# top.net
KiCad netlist of a schematic drawn in Altium Designer
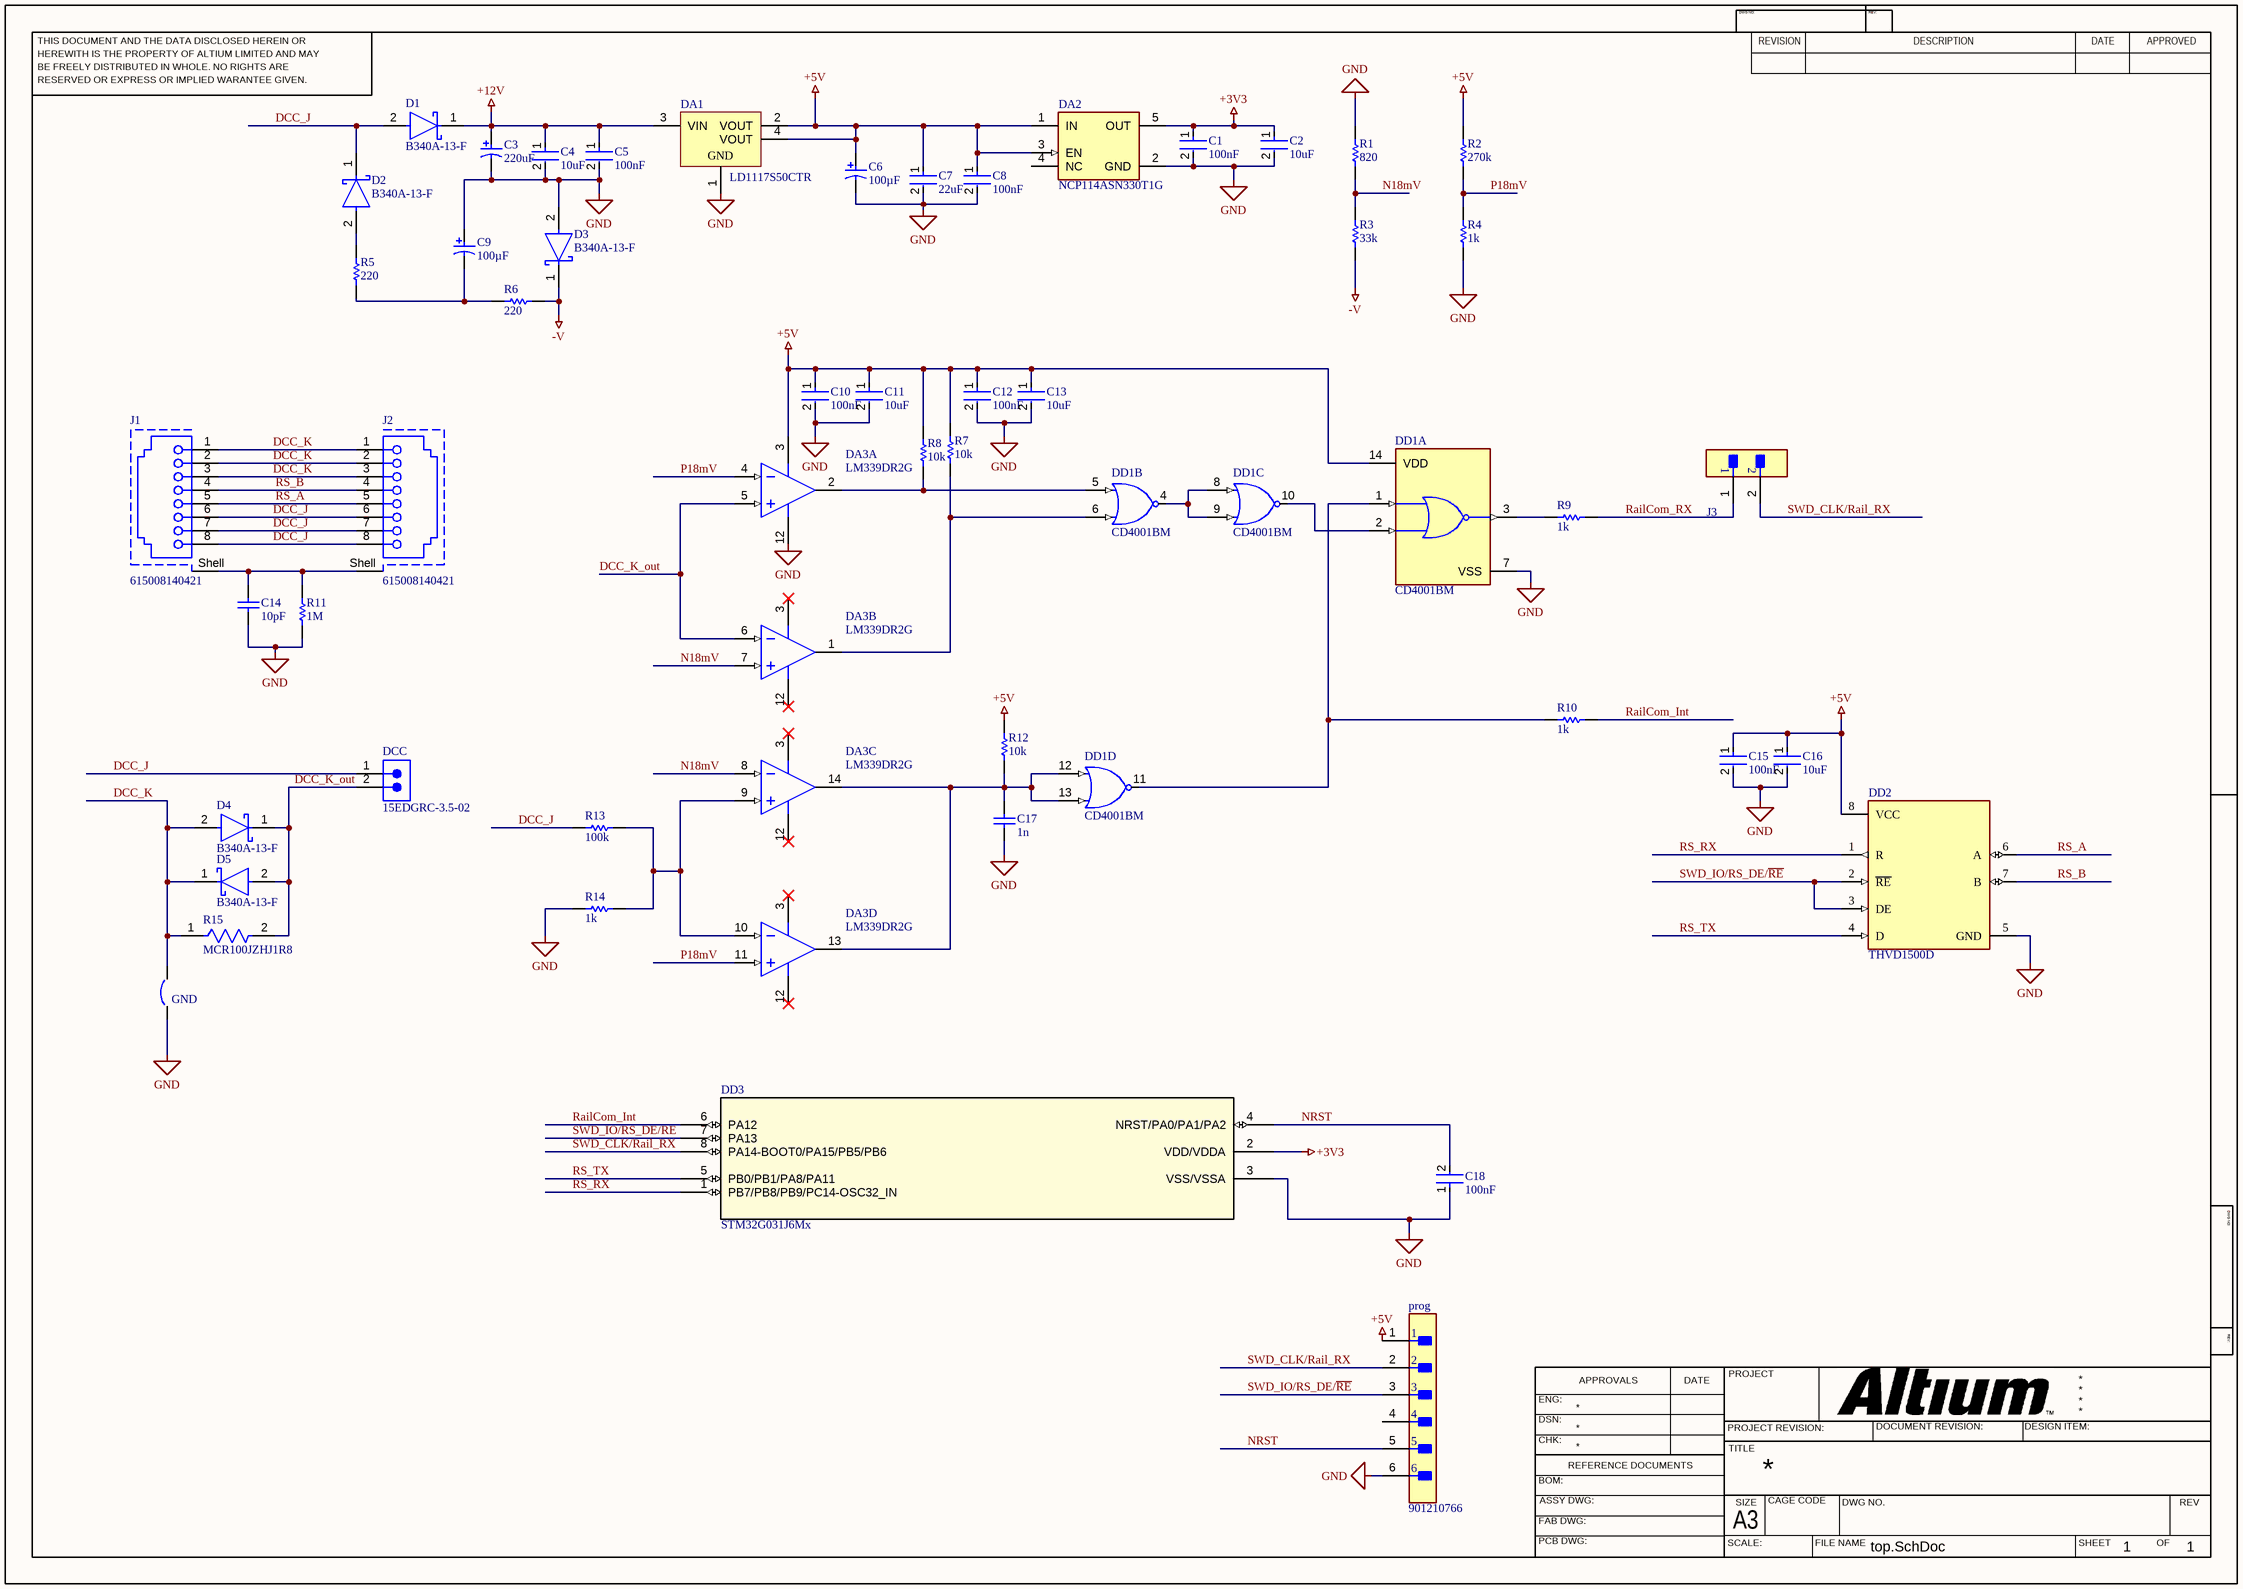
[diagram p0: top.SchDoc]

(export (version "E")
  (design (tool "Eeschema 10.0.6"))
  (components
    (comp (ref "C1")
      (value "CGA3E2X7R1H104K080AA")
      (footprint "FP-CGA3E-0_3-0_1-IPC_C")
      (description "Cap Ceramic 100nF 50V X7R 10% Pad SMD 0603 +125°C Automotive T/R")
      (fields
        (field (name "TOLERANCE") "10%")
        (field (name "CAPACITANCE") "100nF")
        (field (name "VOLTAGE") "50V")
      )
      (libsource (lib "Altium Content Vault") (part "b4654b650e69147ec39a6b967a45e02"))
    )
    (comp (ref "C2")
      (value "GRM188R60J106ME47D")
      (footprint "FP-GRM188-0_1-e0_2_0_55-IPC_C")
      (description "Chip Multilayer Ceramic Capacitors for General Purpose, 0603, 10uF, X5R, 15%, 20%, 6.3V")
      (fields
        (field (name "CAPACITANCE") "10uF")
        (field (name "VOLTAGE") "6.3V")
        (field (name "TOLERANCE") "20%")
      )
      (libsource (lib "Altium Content Vault") (part "02cd4be3c70576c341d710602a673aa"))
    )
    (comp (ref "C3")
      (value "220uF")
      (footprint "PNSC-EEE-FK1E221P_N")
      (fields (field (name "MANUFACTURER") "Panasonic") (field (name "Comment") "EEE-FK1E221P"))
      (libsource (lib "Altium Content Vault") (part "CAP-P-2"))
    )
    (comp (ref "C4")
      (value "GRM188R60J106ME47D")
      (footprint "FP-GRM188-0_1-e0_2_0_55-IPC_C")
      (description "Chip Multilayer Ceramic Capacitors for General Purpose, 0603, 10uF, X5R, 15%, 20%, 6.3V")
      (fields
        (field (name "CAPACITANCE") "10uF")
        (field (name "VOLTAGE") "6.3V")
        (field (name "TOLERANCE") "20%")
      )
      (libsource (lib "Altium Content Vault") (part "02cd4be3c70576c341d710602a673aa"))
    )
    (comp (ref "C5")
      (value "CGA3E2X7R1H104K080AA")
      (footprint "FP-CGA3E-0_3-0_1-IPC_C")
      (description "Cap Ceramic 100nF 50V X7R 10% Pad SMD 0603 +125°C Automotive T/R")
      (fields
        (field (name "TOLERANCE") "10%")
        (field (name "CAPACITANCE") "100nF")
        (field (name "VOLTAGE") "50V")
      )
      (libsource (lib "Altium Content Vault") (part "b4654b650e69147ec39a6b967a45e02"))
    )
    (comp (ref "C6")
      (value "EEEFK1E101XP")
      (footprint "PNSC-FK-V-D8_V")
      (fields (field (name "CAPACITANCE") "100µF") (field (name "MANUFACTURER") "Panasonic"))
      (libsource (lib "Altium Content Vault") (part "CAP-P-2"))
    )
    (comp (ref "C7")
      (value "GRM188R61A226ME15D")
      (footprint "FP-GRM188-0_2-IPC_C")
      (description "Chip Multilayer Ceramic Capacitors for General Purpose, 0603, 22uF, X5R, 15%, 20%, 10V")
      (fields (field (name "TOLERANCE") "20%") (field (name "CAPACITANCE") "22uF"))
      (libsource (lib "Altium Content Vault") (part "11868f565c42a9108669ba33697ecf6"))
    )
    (comp (ref "C8")
      (value "CGA3E2X7R1H104K080AA")
      (footprint "FP-CGA3E-0_3-0_1-IPC_C")
      (description "Cap Ceramic 100nF 50V X7R 10% Pad SMD 0603 +125°C Automotive T/R")
      (fields
        (field (name "TOLERANCE") "10%")
        (field (name "CAPACITANCE") "100nF")
        (field (name "VOLTAGE") "50V")
      )
      (libsource (lib "Altium Content Vault") (part "b4654b650e69147ec39a6b967a45e02"))
    )
    (comp (ref "C9")
      (value "EEEFK1E101XP")
      (footprint "PNSC-FK-V-D8_V")
      (fields (field (name "CAPACITANCE") "100µF") (field (name "MANUFACTURER") "Panasonic"))
      (libsource (lib "Altium Content Vault") (part "CAP-P-2"))
    )
    (comp (ref "C10")
      (value "CGA3E2X7R1H104K080AA")
      (footprint "FP-CGA3E-0_3-0_1-IPC_C")
      (description "Cap Ceramic 100nF 50V X7R 10% Pad SMD 0603 +125°C Automotive T/R")
      (fields
        (field (name "TOLERANCE") "10%")
        (field (name "CAPACITANCE") "100nF")
        (field (name "VOLTAGE") "50V")
      )
      (libsource (lib "Altium Content Vault") (part "b4654b650e69147ec39a6b967a45e02"))
    )
    (comp (ref "C11")
      (value "GRM188R60J106ME47D")
      (footprint "FP-GRM188-0_1-e0_2_0_55-IPC_C")
      (description "Chip Multilayer Ceramic Capacitors for General Purpose, 0603, 10uF, X5R, 15%, 20%, 6.3V")
      (fields
        (field (name "CAPACITANCE") "10uF")
        (field (name "VOLTAGE") "6.3V")
        (field (name "TOLERANCE") "20%")
      )
      (libsource (lib "Altium Content Vault") (part "02cd4be3c70576c341d710602a673aa"))
    )
    (comp (ref "C12")
      (value "CGA3E2X7R1H104K080AA")
      (footprint "FP-CGA3E-0_3-0_1-IPC_C")
      (description "Cap Ceramic 100nF 50V X7R 10% Pad SMD 0603 +125°C Automotive T/R")
      (fields
        (field (name "TOLERANCE") "10%")
        (field (name "CAPACITANCE") "100nF")
        (field (name "VOLTAGE") "50V")
      )
      (libsource (lib "Altium Content Vault") (part "b4654b650e69147ec39a6b967a45e02"))
    )
    (comp (ref "C13")
      (value "GRM188R60J106ME47D")
      (footprint "FP-GRM188-0_1-e0_2_0_55-IPC_C")
      (description "Chip Multilayer Ceramic Capacitors for General Purpose, 0603, 10uF, X5R, 15%, 20%, 6.3V")
      (fields
        (field (name "CAPACITANCE") "10uF")
        (field (name "VOLTAGE") "6.3V")
        (field (name "TOLERANCE") "20%")
      )
      (libsource (lib "Altium Content Vault") (part "02cd4be3c70576c341d710602a673aa"))
    )
    (comp (ref "C14")
      (value "10pF")
      (footprint "CAPC0603(1608)100_N")
      (description "CAP 10pF 25V ±1% 0603 (1608 Metric) Thickness 1mm SMD")
      (fields (field (name "TOLERANCE") "Â±1%") (field (name "Comment") "CAP 10pF 25V 0603(1608)"))
      (libsource (lib "Altium Content Vault") (part "CAP"))
    )
    (comp (ref "C15")
      (value "CGA3E2X7R1H104K080AA")
      (footprint "FP-CGA3E-0_3-0_1-IPC_C")
      (description "Cap Ceramic 100nF 50V X7R 10% Pad SMD 0603 +125°C Automotive T/R")
      (fields
        (field (name "TOLERANCE") "10%")
        (field (name "CAPACITANCE") "100nF")
        (field (name "VOLTAGE") "50V")
      )
      (libsource (lib "Altium Content Vault") (part "b4654b650e69147ec39a6b967a45e02"))
    )
    (comp (ref "C16")
      (value "GRM188R60J106ME47D")
      (footprint "FP-GRM188-0_1-e0_2_0_55-IPC_C")
      (description "Chip Multilayer Ceramic Capacitors for General Purpose, 0603, 10uF, X5R, 15%, 20%, 6.3V")
      (fields
        (field (name "CAPACITANCE") "10uF")
        (field (name "VOLTAGE") "6.3V")
        (field (name "TOLERANCE") "20%")
      )
      (libsource (lib "Altium Content Vault") (part "02cd4be3c70576c341d710602a673aa"))
    )
    (comp (ref "C17")
      (value "1n")
      (footprint "CAPC1608X90X35NL10T15")
      (fields (field (name "PART NUMBER") "GRM188R71H102KA01D") (field (name "MANUFACTURER") "Murata"))
      (libsource (lib "Altium Content Vault") (part "CAP"))
    )
    (comp (ref "C18")
      (value "CGA3E2X7R1H104K080AA")
      (footprint "FP-CGA3E-0_3-0_1-MFG")
      (description "Cap Ceramic 100nF 50V X7R 10% Pad SMD 0603 +125°C Automotive T/R")
      (fields
        (field (name "TOLERANCE") "10%")
        (field (name "CAPACITANCE") "100nF")
        (field (name "VOLTAGE") "50V")
      )
      (libsource (lib "Altium Content Vault") (part "b4654b650e69147ec39a6b967a45e02"))
    )
    (comp (ref "D1")
      (value "B340A-13-F")
      (footprint "FP-SMA-MFG")
      (description "DIODE SCHOTTKY 40V 3A SMA")
      (fields (field (name "VOLTAGE") "40V"))
      (libsource (lib "Altium Content Vault") (part "1d6ec82d83fb6aee721767c19dac4b9"))
    )
    (comp (ref "D2")
      (value "B340A-13-F")
      (footprint "FP-SMA-MFG")
      (description "DIODE SCHOTTKY 40V 3A SMA")
      (fields (field (name "VOLTAGE") "40V"))
      (libsource (lib "Altium Content Vault") (part "1d6ec82d83fb6aee721767c19dac4b9"))
    )
    (comp (ref "D3")
      (value "B340A-13-F")
      (footprint "FP-SMA-MFG")
      (description "DIODE SCHOTTKY 40V 3A SMA")
      (fields (field (name "VOLTAGE") "40V"))
      (libsource (lib "Altium Content Vault") (part "1d6ec82d83fb6aee721767c19dac4b9"))
    )
    (comp (ref "D4")
      (value "B340A-13-F")
      (footprint "FP-SMA-MFG")
      (description "DIODE SCHOTTKY 40V 3A SMA")
      (fields (field (name "VOLTAGE") "40V"))
      (libsource (lib "Altium Content Vault") (part "1d6ec82d83fb6aee721767c19dac4b9"))
    )
    (comp (ref "D5")
      (value "B340A-13-F")
      (footprint "FP-SMA-MFG")
      (description "DIODE SCHOTTKY 40V 3A SMA")
      (fields (field (name "VOLTAGE") "40V"))
      (libsource (lib "Altium Content Vault") (part "1d6ec82d83fb6aee721767c19dac4b9"))
    )
    (comp (ref "DA1")
      (value "LD1117S50CTR")
      (footprint "SOT-223_N")
      (description "Fixed Low Drop Positive Voltage Regulator, 5V, 4-Pin SOT-223, Tape and Reel")
      (libsource (lib "Altium Content Vault") (part "PM-REG-LD1117-SOT4"))
    )
    (comp (ref "DA2")
      (value "NCP114ASN330T1G")
      (footprint "FP-483-MFG")
      (description "IC REG LINEAR 3.3V 300MA 5TSOP")
      (fields
        (field (name "MANUFACTURER") "ON Semiconductor")
        (field (name "OCTOPART") "https://octopart.com/ncp114asn330t1g-on+semiconductor-74628742")
      )
      (libsource (lib "Altium Content Vault") (part "57814aa37072aacea77ef0fe9350350"))
    )
    (comp (ref "DA3")
      (value "LM339DR2G")
      (footprint "ONSC-SOIC-14-751A-03_V")
      (description "Single Supply Quad Comparators, 0 to 70 degC, 14-Pin SOIC, Pb-Free, Tape and Reel")
      (fields (field (name "MANUFACTURER") "On Semiconductor"))
      (libsource (lib "Altium Content Vault") (part "ONSC-LM239_LM339_LM2901_NCV2901_MC3302_LMV339-14"))
    )
    (comp (ref "DCC")
      (value "15EDGRC-3.5-02")
      (footprint "691305140002")
      (libsource (lib "Altium Content Vault") (part "TBL - 1R - 02P - Male"))
    )
    (comp (ref "DD1")
      (value "CD4001BM")
      (footprint "FP-D0014A-MFG")
      (description "IC GATE NOR 4CH 2-INP 14SOIC")
      (libsource (lib "Altium Content Vault") (part "2cf6dc1d20626fb6062ed3edb113d6e"))
    )
    (comp (ref "DD2")
      (value "THVD1500D")
      (footprint "FP-D0008B-IPC_A")
      (description "IC TRANSCEIVER HALF 1/1 8SOIC")
      (libsource (lib "Altium Content Vault") (part "2959008ed950a7d942df01a48597072"))
    )
    (comp (ref "DD3")
      (value "STM32G031J6Mx")
      (footprint "SO-8")
      (fields
        (field (name "MANUFACTURER_PART_NUMBER") "stm32g0_so8_t1")
        (field (name "COPYRIGHT") "Copyright (C) 2018 Accelerated Designs. All rights reserved")
      )
      (libsource (lib "ST Microelectronics STM32 G0") (part "STM32G031J6Mx"))
    )
    (comp (ref "GND")
      (value "~")
      (footprint "JP_SMD")
      (description "Circuit Breaker")
      (fields (field (name "PUBLISHER") "Altium Limited"))
      (libsource (lib "test_adc") (part "Circuit Breaker"))
    )
    (comp (ref "J1")
      (value "615008140421")
      (footprint "615008140421")
      (libsource (lib "Altium Content Vault") (part "8P8C - 1 Port - Shielded"))
    )
    (comp (ref "J2")
      (value "615008140421")
      (footprint "615008140421")
      (libsource (lib "Altium Content Vault") (part "8P8C - 1 Port - Shielded"))
    )
    (comp (ref "J3")
      (value "M20-9990245")
      (footprint "FP-M20-9990245-MFG")
      (description "CONN HEADER VERT 2POS 2.54MM")
      (fields (field (name "VOLTAGE") "50V"))
      (libsource (lib "Altium Content Vault") (part "3bc925449376181038e59eaffc5286c"))
    )
    (comp (ref "prog")
      (value "901210766")
      (footprint "FP-901210766-MFG")
      (description "CONN HEADER R/A 6POS 2.54MM")
      (fields
        (field (name "MANUFACTURER") "Molex")
        (field (name "OCTOPART") "https://octopart.com/90121-0766-molex-655456")
      )
      (libsource (lib "Altium Content Vault") (part "f2cb566baf1c37ab5a3b8e90bbeafd6"))
    )
    (comp (ref "R1")
      (value "820")
      (footprint "RESC1608X55X30NL15T15")
      (fields (field (name "MANUFACTURER") "Panasonic") (field (name "PART NUMBER") "ERJ3EKF8203V"))
      (libsource (lib "Altium Content Vault") (part "RES"))
    )
    (comp (ref "R2")
      (value "270k")
      (footprint "RESC1608X55X30NL20T10")
      (fields (field (name "PART NUMBER") "RK73H1JTTD2703F") (field (name "MANUFACTURER") "KOA Speer"))
      (libsource (lib "Altium Content Vault") (part "RES"))
    )
    (comp (ref "R3")
      (value "33k")
      (footprint "RESC1608X55X30NL20T20")
      (fields (field (name "PART NUMBER") "ERA3AEB333V") (field (name "MANUFACTURER") "Panasonic"))
      (libsource (lib "Altium Content Vault") (part "RES"))
    )
    (comp (ref "R4")
      (value "1k")
      (footprint "RESC1608X55X30NL15T15")
      (fields (field (name "PART NUMBER") "ERJ-3EKF1001V") (field (name "MANUFACTURER") "Panasonic"))
      (libsource (lib "Altium Content Vault") (part "RES"))
    )
    (comp (ref "R5")
      (value "220")
      (footprint "RESC1608X55X30NL15T15")
      (description "Chip Resistor, 220 Ohm, +/- 1%, 0.1 W, -55 to 155 degC, 0603 (1608 Metric), RoHS, Tape and Reel")
      (fields (field (name "TOLERANCE") "1%") (field (name "Comment") "ERJ-3EKF2200V"))
      (libsource (lib "Altium Content Vault") (part "RES-2"))
    )
    (comp (ref "R6")
      (value "220")
      (footprint "RESC1608X55X30NL15T15")
      (description "Chip Resistor, 220 Ohm, +/- 1%, 0.1 W, -55 to 155 degC, 0603 (1608 Metric), RoHS, Tape and Reel")
      (fields (field (name "TOLERANCE") "1%") (field (name "Comment") "ERJ-3EKF2200V"))
      (libsource (lib "Altium Content Vault") (part "RES-2"))
    )
    (comp (ref "R7")
      (value "10k")
      (footprint "RESC1609X55X30NL15T15")
      (description "Chip Resistor, 10 KOhm, +/- 1%, 0.1 W, -55 to 155 degC, 0603 (1608 Metric), RoHS, Tape and Reel")
      (fields (field (name "TOLERANCE") "1%") (field (name "MANUFACTURER") "Panasonic"))
      (libsource (lib "Altium Content Vault") (part "RES-2"))
    )
    (comp (ref "R8")
      (value "10k")
      (footprint "RESC1609X55X30NL15T15")
      (description "Chip Resistor, 10 KOhm, +/- 1%, 0.1 W, -55 to 155 degC, 0603 (1608 Metric), RoHS, Tape and Reel")
      (fields (field (name "TOLERANCE") "1%") (field (name "MANUFACTURER") "Panasonic"))
      (libsource (lib "Altium Content Vault") (part "RES-2"))
    )
    (comp (ref "R9")
      (value "1k")
      (footprint "RESC1608X55X30NL15T15")
      (fields (field (name "PART NUMBER") "ERJ-3EKF1001V") (field (name "MANUFACTURER") "Panasonic"))
      (libsource (lib "Altium Content Vault") (part "RES"))
    )
    (comp (ref "R10")
      (value "1k")
      (footprint "RESC1608X55X30NL15T15")
      (fields (field (name "PART NUMBER") "ERJ-3EKF1001V") (field (name "MANUFACTURER") "Panasonic"))
      (libsource (lib "Altium Content Vault") (part "RES"))
    )
    (comp (ref "R11")
      (value "1M")
      (footprint "RESC1608X55X25NL10T15")
      (description "Chip Resistor, 1 MOhm, +/- 1%, 100 mW, -55 to 155 degC, 0603 (1608 Metric), RoHS, Tape and Reel")
      (fields (field (name "TOLERANCE") "20%") (field (name "Comment") "RC0603FR-071ML"))
      (libsource (lib "Altium Content Vault") (part "RES-2"))
    )
    (comp (ref "R12")
      (value "10k")
      (footprint "RESC1609X55X30NL15T15")
      (description "Chip Resistor, 10 KOhm, +/- 1%, 0.1 W, -55 to 155 degC, 0603 (1608 Metric), RoHS, Tape and Reel")
      (fields (field (name "TOLERANCE") "1%") (field (name "MANUFACTURER") "Panasonic"))
      (libsource (lib "Altium Content Vault") (part "RES-2"))
    )
    (comp (ref "R13")
      (value "100k")
      (footprint "RESC1608X55X30NL15T15")
      (fields (field (name "PART NUMBER") "ERJ-3EKF1003V") (field (name "MANUFACTURER") "Panasonic"))
      (libsource (lib "Altium Content Vault") (part "RES"))
    )
    (comp (ref "R14")
      (value "1k")
      (footprint "RESC1608X55X30NL15T15")
      (fields (field (name "PART NUMBER") "ERJ-3EKF1001V") (field (name "MANUFACTURER") "Panasonic"))
      (libsource (lib "Altium Content Vault") (part "RES"))
    )
    (comp (ref "R15")
      (value "MCR100JZHJ1R8")
      (footprint "FP-MCR100-IPC_C")
      (description "Thick Film Chip Resistor, 2512, 1.8Ω, 5%, +850/+150ppm/°C, 1W, 200V")
      (fields (field (name "TOLERANCE") "5%"))
      (libsource (lib "Altium Content Vault") (part "1029c3af85768c4190bb7ad29bc67b5"))
    )
  )
  (nets
    (net (code "1") (name "+3V3") (class "Default")
      (node (ref "C1") (pin "1") (pinfunction "1_1") (pintype "passive"))
      (node (ref "C2") (pin "1") (pinfunction "1_1") (pintype "passive"))
      (node (ref "DA2") (pin "5") (pinfunction "OUT_5") (pintype "power_in"))
      (node (ref "DD3") (pin "2") (pinfunction "VDD/VDDA_2") (pintype "power_in"))
    )
    (net (code "2") (name "+5V") (class "Default")
      (node (ref "C10") (pin "1") (pinfunction "1_1") (pintype "passive"))
      (node (ref "C11") (pin "1") (pinfunction "1_1") (pintype "passive"))
      (node (ref "C12") (pin "1") (pinfunction "1_1") (pintype "passive"))
      (node (ref "C13") (pin "1") (pinfunction "1_1") (pintype "passive"))
      (node (ref "C15") (pin "1") (pinfunction "1_1") (pintype "passive"))
      (node (ref "C16") (pin "1") (pinfunction "1_1") (pintype "passive"))
      (node (ref "C6") (pin "1") (pinfunction "1_1") (pintype "passive"))
      (node (ref "C7") (pin "1") (pinfunction "1_1") (pintype "passive"))
      (node (ref "C8") (pin "1") (pinfunction "1_1") (pintype "passive"))
      (node (ref "DA1") (pin "2") (pinfunction "VOUT_2") (pintype "power_in"))
      (node (ref "DA1") (pin "4") (pinfunction "VOUT_4") (pintype "power_in"))
      (node (ref "DA2") (pin "1") (pinfunction "IN_1") (pintype "power_in"))
      (node (ref "DA2") (pin "3") (pinfunction "EN_3") (pintype "input"))
      (node (ref "DA3") (pin "3") (pinfunction "VCC_3") (pintype "power_in"))
      (node (ref "DD1") (pin "14") (pinfunction "VDD_14") (pintype "power_in"))
      (node (ref "DD2") (pin "8") (pinfunction "VCC_8") (pintype "power_in"))
      (node (ref "R12") (pin "1") (pinfunction "1_1") (pintype "passive"))
      (node (ref "R2") (pin "2") (pinfunction "2_2") (pintype "passive"))
      (node (ref "R7") (pin "1") (pinfunction "1_1") (pintype "passive"))
      (node (ref "R8") (pin "1") (pinfunction "1_1") (pintype "passive"))
      (node (ref "prog") (pin "1") (pinfunction "1_1") (pintype "passive"))
    )
    (net (code "3") (name "+12V") (class "Default")
      (node (ref "C3") (pin "1") (pinfunction "1_1") (pintype "passive"))
      (node (ref "C4") (pin "1") (pinfunction "1_1") (pintype "passive"))
      (node (ref "C5") (pin "1") (pinfunction "1_1") (pintype "passive"))
      (node (ref "D1") (pin "1") (pinfunction "C_1") (pintype "passive"))
      (node (ref "DA1") (pin "3") (pinfunction "VIN_3") (pintype "power_in"))
    )
    (net (code "4") (name "-V") (class "Default")
      (node (ref "D3") (pin "1") (pinfunction "C_1") (pintype "passive"))
      (node (ref "R3") (pin "1") (pinfunction "1_1") (pintype "passive"))
      (node (ref "R6") (pin "2") (pinfunction "2_2") (pintype "passive"))
    )
    (net (code "6") (name "/DCC_J") (class "Default")
      (node (ref "D1") (pin "2") (pinfunction "A_2") (pintype "passive"))
      (node (ref "D2") (pin "1") (pinfunction "C_1") (pintype "passive"))
      (node (ref "DCC") (pin "1") (pinfunction "1_1") (pintype "passive"))
      (node (ref "J1") (pin "6") (pinfunction "6_6") (pintype "passive"))
      (node (ref "J1") (pin "7") (pinfunction "7_7") (pintype "passive"))
      (node (ref "J1") (pin "8") (pinfunction "8_8") (pintype "passive"))
      (node (ref "J2") (pin "6") (pinfunction "6_6") (pintype "passive"))
      (node (ref "J2") (pin "7") (pinfunction "7_7") (pintype "passive"))
      (node (ref "J2") (pin "8") (pinfunction "8_8") (pintype "passive"))
      (node (ref "R13") (pin "2") (pinfunction "2_2") (pintype "passive"))
    )
    (net (code "7") (name "/DCC_K") (class "Default")
      (node (ref "D4") (pin "2") (pinfunction "A_2") (pintype "passive"))
      (node (ref "D5") (pin "1") (pinfunction "C_1") (pintype "passive"))
      (node (ref "GND") (pin "2") (pinfunction "2_2") (pintype "passive"))
      (node (ref "J1") (pin "1") (pinfunction "1_1") (pintype "passive"))
      (node (ref "J1") (pin "2") (pinfunction "2_2") (pintype "passive"))
      (node (ref "J1") (pin "3") (pinfunction "3_3") (pintype "passive"))
      (node (ref "J2") (pin "1") (pinfunction "1_1") (pintype "passive"))
      (node (ref "J2") (pin "2") (pinfunction "2_2") (pintype "passive"))
      (node (ref "J2") (pin "3") (pinfunction "3_3") (pintype "passive"))
      (node (ref "R15") (pin "1") (pinfunction "1_1") (pintype "passive"))
    )
    (net (code "8") (name "/DCC_K_out") (class "Default")
      (node (ref "D4") (pin "1") (pinfunction "C_1") (pintype "passive"))
      (node (ref "D5") (pin "2") (pinfunction "A_2") (pintype "passive"))
      (node (ref "DA3") (pin "5") (pinfunction "IN1+_5") (pintype "input"))
      (node (ref "DA3") (pin "6") (pinfunction "IN2-_6") (pintype "input"))
      (node (ref "DCC") (pin "2") (pinfunction "2_2") (pintype "passive"))
      (node (ref "R15") (pin "2") (pinfunction "2_2") (pintype "passive"))
    )
    (net (code "9") (name "/N18mV") (class "Default")
      (node (ref "DA3") (pin "7") (pinfunction "IN2+_7") (pintype "input"))
      (node (ref "DA3") (pin "8") (pinfunction "IN3-_8") (pintype "input"))
      (node (ref "R1") (pin "1") (pinfunction "1_1") (pintype "passive"))
      (node (ref "R3") (pin "2") (pinfunction "2_2") (pintype "passive"))
    )
    (net (code "10") (name "/NRST") (class "Default")
      (node (ref "C18") (pin "2") (pinfunction "2_2") (pintype "passive"))
      (node (ref "DD3") (pin "4") (pinfunction "NRST/PA0/PA1/PA2_4") (pintype "bidirectional"))
      (node (ref "prog") (pin "5") (pinfunction "5_5") (pintype "passive"))
    )
    (net (code "11") (name "/P18mV") (class "Default")
      (node (ref "DA3") (pin "11") (pinfunction "IN4+_11") (pintype "input"))
      (node (ref "DA3") (pin "4") (pinfunction "IN1-_4") (pintype "input"))
      (node (ref "R2") (pin "1") (pinfunction "1_1") (pintype "passive"))
      (node (ref "R4") (pin "2") (pinfunction "2_2") (pintype "passive"))
    )
    (net (code "12") (name "/RS_A") (class "Default")
      (node (ref "DD2") (pin "6") (pinfunction "A_6") (pintype "bidirectional"))
      (node (ref "J1") (pin "5") (pinfunction "5_5") (pintype "passive"))
      (node (ref "J2") (pin "5") (pinfunction "5_5") (pintype "passive"))
    )
    (net (code "13") (name "/RS_B") (class "Default")
      (node (ref "DD2") (pin "7") (pinfunction "B_7") (pintype "bidirectional"))
      (node (ref "J1") (pin "4") (pinfunction "4_4") (pintype "passive"))
      (node (ref "J2") (pin "4") (pinfunction "4_4") (pintype "passive"))
    )
    (net (code "14") (name "/RS_RX") (class "Default")
      (node (ref "DD2") (pin "1") (pinfunction "R_1") (pintype "output"))
      (node (ref "DD3") (pin "1") (pinfunction "PB7/PB8/PB9/PC14-OSC32_IN_1") (pintype "bidirectional"))
    )
    (net (code "15") (name "/RS_TX") (class "Default")
      (node (ref "DD2") (pin "4") (pinfunction "D_4") (pintype "input"))
      (node (ref "DD3") (pin "5") (pinfunction "PB0/PB1/PA8/PA11_5") (pintype "bidirectional"))
    )
    (net (code "16") (name "/RailCom_Int") (class "Default")
      (node (ref "DD3") (pin "6") (pinfunction "PA12_6") (pintype "bidirectional"))
      (node (ref "R10") (pin "1") (pinfunction "1_1") (pintype "passive"))
    )
    (net (code "17") (name "/RailCom_RX") (class "Default")
      (node (ref "J3") (pin "1") (pinfunction "1_1") (pintype "passive"))
      (node (ref "R9") (pin "1") (pinfunction "1_1") (pintype "passive"))
    )
    (net (code "18") (name "/SWD_CLK{slash}Rail_RX") (class "Default")
      (node (ref "DD3") (pin "8") (pinfunction "PA14-BOOT0/PA15/PB5/PB6_8") (pintype "bidirectional"))
      (node (ref "J3") (pin "2") (pinfunction "2_2") (pintype "passive"))
      (node (ref "prog") (pin "2") (pinfunction "2_2") (pintype "passive"))
    )
    (net (code "19") (name "/SWD_IO{slash}RS_DE{slash}~{RE}") (class "Default")
      (node (ref "DD2") (pin "2") (pinfunction "~{RE}_2") (pintype "input"))
      (node (ref "DD2") (pin "3") (pinfunction "DE_3") (pintype "input"))
      (node (ref "DD3") (pin "7") (pinfunction "PA13_7") (pintype "bidirectional"))
      (node (ref "prog") (pin "3") (pinfunction "3_3") (pintype "passive"))
    )
    (net (code "20") (name "GND") (class "Default")
      (node (ref "C1") (pin "2") (pinfunction "2_2") (pintype "passive"))
      (node (ref "C10") (pin "2") (pinfunction "2_2") (pintype "passive"))
      (node (ref "C11") (pin "2") (pinfunction "2_2") (pintype "passive"))
      (node (ref "C12") (pin "2") (pinfunction "2_2") (pintype "passive"))
      (node (ref "C13") (pin "2") (pinfunction "2_2") (pintype "passive"))
      (node (ref "C14") (pin "2") (pinfunction "2_2") (pintype "passive"))
      (node (ref "C15") (pin "2") (pinfunction "2_2") (pintype "passive"))
      (node (ref "C16") (pin "2") (pinfunction "2_2") (pintype "passive"))
      (node (ref "C17") (pin "1") (pinfunction "1_1") (pintype "passive"))
      (node (ref "C18") (pin "1") (pinfunction "1_1") (pintype "passive"))
      (node (ref "C2") (pin "2") (pinfunction "2_2") (pintype "passive"))
      (node (ref "C3") (pin "2") (pinfunction "2_2") (pintype "passive"))
      (node (ref "C4") (pin "2") (pinfunction "2_2") (pintype "passive"))
      (node (ref "C5") (pin "2") (pinfunction "2_2") (pintype "passive"))
      (node (ref "C6") (pin "2") (pinfunction "2_2") (pintype "passive"))
      (node (ref "C7") (pin "2") (pinfunction "2_2") (pintype "passive"))
      (node (ref "C8") (pin "2") (pinfunction "2_2") (pintype "passive"))
      (node (ref "C9") (pin "1") (pinfunction "1_1") (pintype "passive"))
      (node (ref "D3") (pin "2") (pinfunction "A_2") (pintype "passive"))
      (node (ref "DA1") (pin "1") (pinfunction "GND_1") (pintype "power_in"))
      (node (ref "DA2") (pin "2") (pinfunction "GND_2") (pintype "power_in"))
      (node (ref "DA3") (pin "12") (pinfunction "GND_12") (pintype "power_in"))
      (node (ref "DD1") (pin "7") (pinfunction "VSS_7") (pintype "power_in"))
      (node (ref "DD2") (pin "5") (pinfunction "GND_5") (pintype "power_in"))
      (node (ref "DD3") (pin "3") (pinfunction "VSS/VSSA_3") (pintype "power_in"))
      (node (ref "GND") (pin "1") (pinfunction "1_1") (pintype "passive"))
      (node (ref "R1") (pin "2") (pinfunction "2_2") (pintype "passive"))
      (node (ref "R11") (pin "2") (pinfunction "2_2") (pintype "passive"))
      (node (ref "R14") (pin "2") (pinfunction "2_2") (pintype "passive"))
      (node (ref "R4") (pin "1") (pinfunction "1_1") (pintype "passive"))
      (node (ref "prog") (pin "6") (pinfunction "6_6") (pintype "passive"))
    )
    (net (code "21") (name "Net-(C9-Pad2)") (class "Default")
      (node (ref "C9") (pin "2") (pinfunction "2_2") (pintype "passive"))
      (node (ref "R5") (pin "1") (pinfunction "1_1") (pintype "passive"))
      (node (ref "R6") (pin "1") (pinfunction "1_1") (pintype "passive"))
    )
    (net (code "22") (name "Net-(C14-Pad1)") (class "Default")
      (node (ref "C14") (pin "1") (pinfunction "1_1") (pintype "passive"))
      (node (ref "J1") (pin "Shell") (pinfunction "Shell_Shell") (pintype "passive"))
      (node (ref "J2") (pin "Shell") (pinfunction "Shell_Shell") (pintype "passive"))
      (node (ref "R11") (pin "1") (pinfunction "1_1") (pintype "passive"))
    )
    (net (code "23") (name "Net-(D2-A)") (class "Default")
      (node (ref "D2") (pin "2") (pinfunction "A_2") (pintype "passive"))
      (node (ref "R5") (pin "2") (pinfunction "2_2") (pintype "passive"))
    )
    (net (code "24") (name "Net-(DA3A-OUT1)") (class "Default")
      (node (ref "DA3") (pin "2") (pinfunction "OUT1_2") (pintype "open_collector"))
      (node (ref "DD1") (pin "5") (pinfunction "C_5") (pintype "input"))
      (node (ref "R8") (pin "2") (pinfunction "2_2") (pintype "passive"))
    )
    (net (code "25") (name "Net-(DA3B-OUT2)") (class "Default")
      (node (ref "DA3") (pin "1") (pinfunction "OUT2_1") (pintype "open_collector"))
      (node (ref "DD1") (pin "6") (pinfunction "D_6") (pintype "input"))
      (node (ref "R7") (pin "2") (pinfunction "2_2") (pintype "passive"))
    )
    (net (code "26") (name "Net-(DA3C-IN3+)") (class "Default")
      (node (ref "DA3") (pin "10") (pinfunction "IN4-_10") (pintype "input"))
      (node (ref "DA3") (pin "9") (pinfunction "IN3+_9") (pintype "input"))
      (node (ref "R13") (pin "1") (pinfunction "1_1") (pintype "passive"))
      (node (ref "R14") (pin "1") (pinfunction "1_1") (pintype "passive"))
    )
    (net (code "27") (name "Net-(DA3C-OUT3)") (class "Default")
      (node (ref "C17") (pin "2") (pinfunction "2_2") (pintype "passive"))
      (node (ref "DA3") (pin "13") (pinfunction "OUT4_13") (pintype "open_collector"))
      (node (ref "DA3") (pin "14") (pinfunction "OUT3_14") (pintype "open_collector"))
      (node (ref "DD1") (pin "12") (pinfunction "G_12") (pintype "input"))
      (node (ref "DD1") (pin "13") (pinfunction "H_13") (pintype "input"))
      (node (ref "R12") (pin "2") (pinfunction "2_2") (pintype "passive"))
    )
    (net (code "28") (name "Net-(DD1A-A)") (class "Default")
      (node (ref "DD1") (pin "1") (pinfunction "A_1") (pintype "input"))
      (node (ref "DD1") (pin "11") (pinfunction "M_11") (pintype "output"))
      (node (ref "R10") (pin "2") (pinfunction "2_2") (pintype "passive"))
    )
    (net (code "29") (name "Net-(DD1A-B)") (class "Default")
      (node (ref "DD1") (pin "10") (pinfunction "L_10") (pintype "output"))
      (node (ref "DD1") (pin "2") (pinfunction "B_2") (pintype "input"))
    )
    (net (code "30") (name "Net-(DD1A-J)") (class "Default")
      (node (ref "DD1") (pin "3") (pinfunction "J_3") (pintype "output"))
      (node (ref "R9") (pin "2") (pinfunction "2_2") (pintype "passive"))
    )
    (net (code "31") (name "Net-(DD1B-K)") (class "Default")
      (node (ref "DD1") (pin "4") (pinfunction "K_4") (pintype "output"))
      (node (ref "DD1") (pin "8") (pinfunction "E_8") (pintype "input"))
      (node (ref "DD1") (pin "9") (pinfunction "F_9") (pintype "input"))
    )
    (net (code "32") (name "unconnected-(DA2-NC-Pad4)") (class "Default")
      (node (ref "DA2") (pin "4") (pinfunction "NC_4") (pintype "passive"))
    )
    (net (code "33") (name "unconnected-(DA3B-GND-Pad12)") (class "Default")
      (node (ref "DA3") (pin "12") (pinfunction "GND_12") (pintype "power_in+no_connect"))
    )
    (net (code "34") (name "unconnected-(DA3B-VCC-Pad3)") (class "Default")
      (node (ref "DA3") (pin "3") (pinfunction "VCC_3") (pintype "power_in+no_connect"))
    )
    (net (code "35") (name "unconnected-(DA3C-GND-Pad12)") (class "Default")
      (node (ref "DA3") (pin "12") (pinfunction "GND_12") (pintype "power_in+no_connect"))
    )
    (net (code "36") (name "unconnected-(DA3C-VCC-Pad3)") (class "Default")
      (node (ref "DA3") (pin "3") (pinfunction "VCC_3") (pintype "power_in+no_connect"))
    )
    (net (code "37") (name "unconnected-(DA3D-GND-Pad12)") (class "Default")
      (node (ref "DA3") (pin "12") (pinfunction "GND_12") (pintype "power_in+no_connect"))
    )
    (net (code "38") (name "unconnected-(DA3D-VCC-Pad3)") (class "Default")
      (node (ref "DA3") (pin "3") (pinfunction "VCC_3") (pintype "power_in+no_connect"))
    )
    (net (code "39") (name "unconnected-(prog-Pad4)") (class "Default")
      (node (ref "prog") (pin "4") (pinfunction "4_4") (pintype "passive"))
    )
  )
)
